# ME433_2017_PCB_mk2.net
KiCad netlist of a schematic drawn in EAGLE
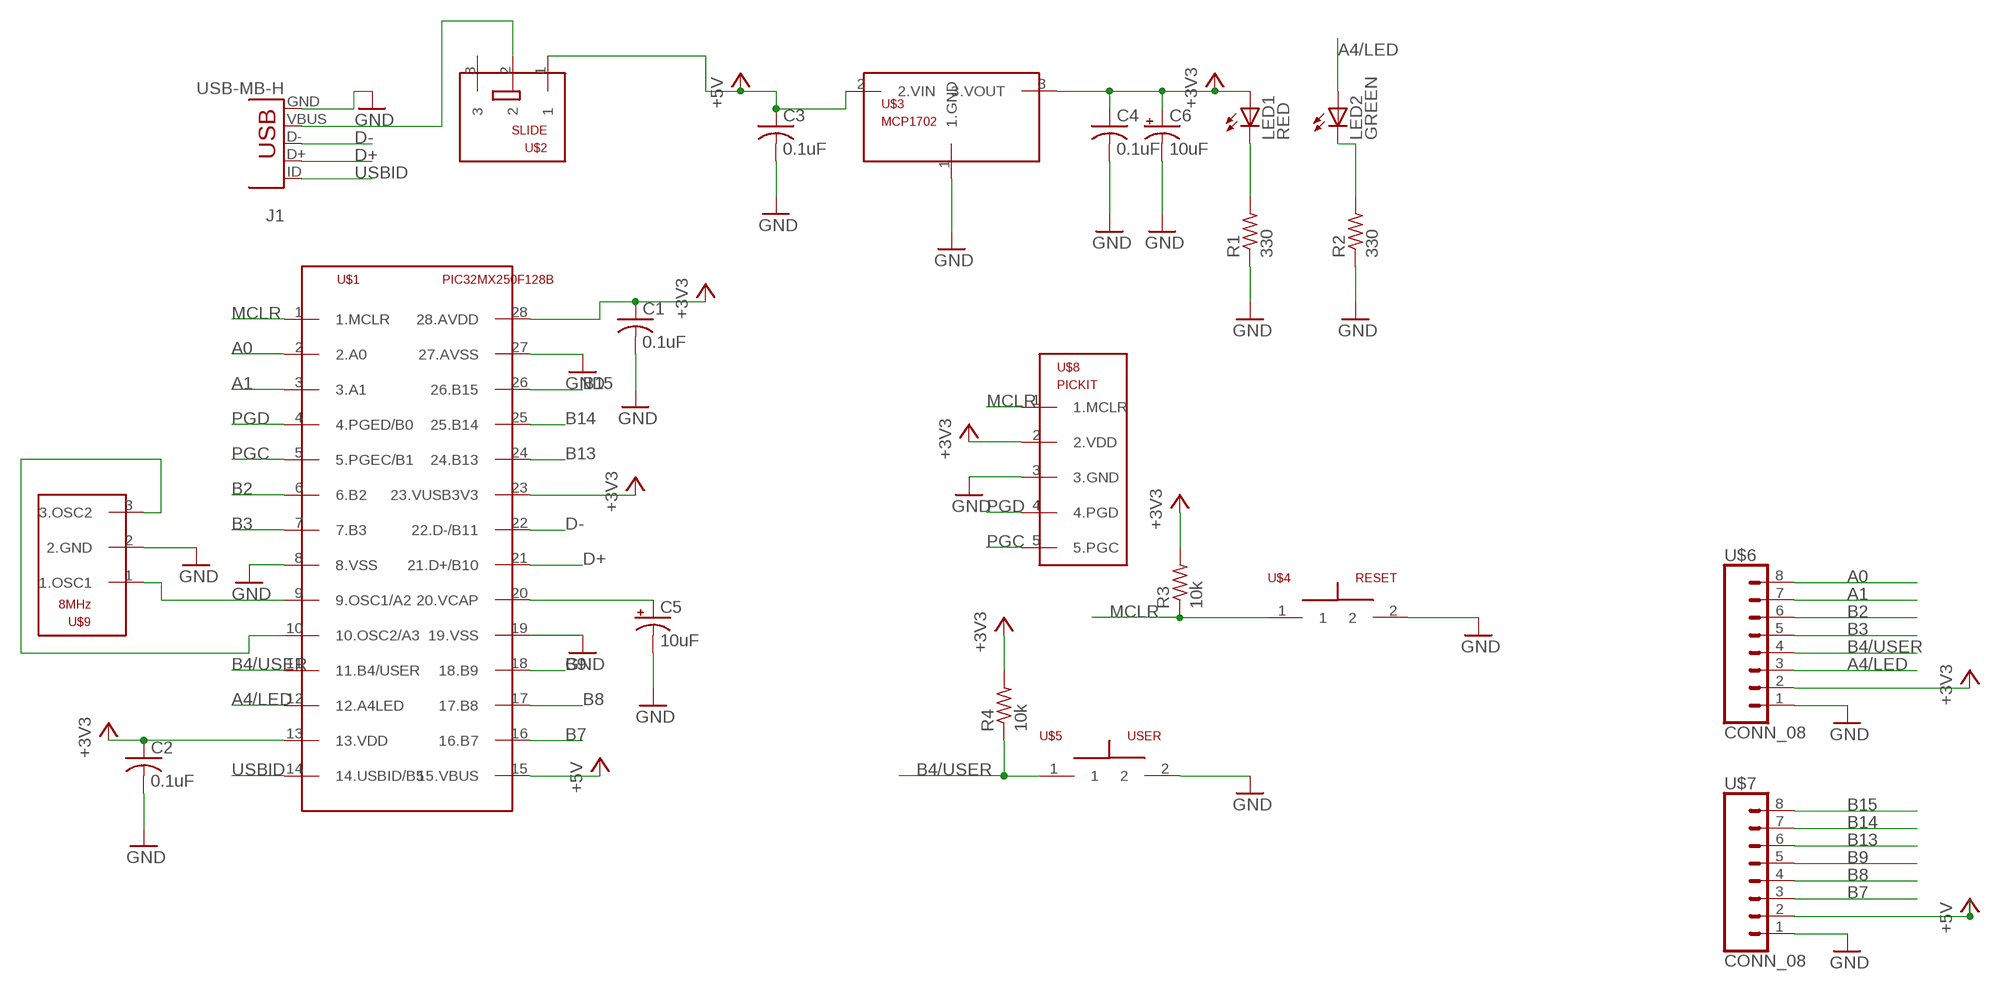
[diagram p0: schematic, sheet 1]

(export (version "E")
  (design (tool "Eeschema 10.0.6"))
  (components
    (comp (ref "C1")
      (value "0.1uF")
      (footprint "eagle-import:C025-025X050")
      (libsource (lib "eagle-import") (part "C-US025-025X050"))
    )
    (comp (ref "C2")
      (value "0.1uF")
      (footprint "eagle-import:C025-025X050")
      (libsource (lib "eagle-import") (part "C-US025-025X050"))
    )
    (comp (ref "C3")
      (value "0.1uF")
      (footprint "eagle-import:C025-025X050")
      (libsource (lib "eagle-import") (part "C-US025-025X050"))
    )
    (comp (ref "C4")
      (value "0.1uF")
      (footprint "eagle-import:C025-025X050")
      (libsource (lib "eagle-import") (part "C-US025-025X050"))
    )
    (comp (ref "C5")
      (value "10uF")
      (footprint "eagle-import:B45181B")
      (libsource (lib "eagle-import") (part "CPOL-USB45181B"))
    )
    (comp (ref "C6")
      (value "10uF")
      (footprint "eagle-import:B45181B")
      (libsource (lib "eagle-import") (part "CPOL-USB45181B"))
    )
    (comp (ref "J1")
      (value "USB-MB-H")
      (footprint "eagle-import:USB-MB-H")
      (libsource (lib "eagle-import") (part "USB-MB-H"))
    )
    (comp (ref "LED1")
      (value "RED")
      (footprint "eagle-import:LED3MM")
      (libsource (lib "eagle-import") (part "LED3MM"))
    )
    (comp (ref "LED2")
      (value "GREEN")
      (footprint "eagle-import:LED3MM")
      (libsource (lib "eagle-import") (part "LED3MM"))
    )
    (comp (ref "R1")
      (value "330")
      (footprint "eagle-import:0207_10")
      (libsource (lib "eagle-import") (part "R-US_0207/10"))
    )
    (comp (ref "R2")
      (value "330")
      (footprint "eagle-import:0207_10")
      (libsource (lib "eagle-import") (part "R-US_0207/10"))
    )
    (comp (ref "R3")
      (value "10k")
      (footprint "eagle-import:0207_10")
      (libsource (lib "eagle-import") (part "R-US_0207/10"))
    )
    (comp (ref "R4")
      (value "10k")
      (footprint "eagle-import:0207_10")
      (libsource (lib "eagle-import") (part "R-US_0207/10"))
    )
    (comp (ref "U$1")
      (value "PIC32MX250F128B")
      (footprint "eagle-import:DIL28-3")
      (libsource (lib "eagle-import") (part "PIC32MX250F128B"))
    )
    (comp (ref "U$2")
      (value "SLIDE")
      (footprint "eagle-import:SLIDE")
      (libsource (lib "eagle-import") (part "SLIDE"))
    )
    (comp (ref "U$3")
      (value "MCP1702")
      (footprint "eagle-import:TO92")
      (libsource (lib "eagle-import") (part "MCP1702"))
    )
    (comp (ref "U$4")
      (value "RESET")
      (footprint "eagle-import:BUTTON")
      (libsource (lib "eagle-import") (part "BUTTON"))
    )
    (comp (ref "U$5")
      (value "USER")
      (footprint "eagle-import:BUTTON")
      (libsource (lib "eagle-import") (part "BUTTON"))
    )
    (comp (ref "U$6")
      (value "CONN_08")
      (footprint "eagle-import:1X08")
      (libsource (lib "eagle-import") (part "CONN_08"))
    )
    (comp (ref "U$7")
      (value "CONN_08")
      (footprint "eagle-import:1X08")
      (libsource (lib "eagle-import") (part "CONN_08"))
    )
    (comp (ref "U$8")
      (value "PICKIT")
      (footprint "eagle-import:1X05")
      (libsource (lib "eagle-import") (part "PICKIT"))
    )
    (comp (ref "U$9")
      (value "8MHz")
      (footprint "eagle-import:OSC")
      (libsource (lib "eagle-import") (part "OSC"))
    )
  )
  (nets
    (net (code "1") (name "+3V3") (class "Default")
      (node (ref "C1") (pin "1") (pinfunction "1_1") (pintype "passive"))
      (node (ref "C2") (pin "1") (pinfunction "1_1") (pintype "passive"))
      (node (ref "C4") (pin "1") (pinfunction "1_1") (pintype "passive"))
      (node (ref "C6") (pin "+") (pinfunction "+_+") (pintype "passive"))
      (node (ref "LED1") (pin "A") (pinfunction "A_A") (pintype "passive"))
      (node (ref "R3") (pin "2") (pinfunction "2_2") (pintype "passive"))
      (node (ref "R4") (pin "2") (pinfunction "2_2") (pintype "passive"))
      (node (ref "U$1") (pin "13") (pinfunction "13.VDD_13") (pintype "bidirectional"))
      (node (ref "U$1") (pin "23") (pinfunction "23.VUSB3V3_23") (pintype "bidirectional"))
      (node (ref "U$1") (pin "28") (pinfunction "28.AVDD_28") (pintype "bidirectional"))
      (node (ref "U$3") (pin "3") (pinfunction "3.VOUT_3") (pintype "bidirectional"))
      (node (ref "U$6") (pin "2") (pinfunction "2_2") (pintype "passive"))
      (node (ref "U$8") (pin "2") (pinfunction "2.VDD_2") (pintype "bidirectional"))
    )
    (net (code "2") (name "+5V") (class "Default")
      (node (ref "C3") (pin "1") (pinfunction "1_1") (pintype "passive"))
      (node (ref "U$1") (pin "15") (pinfunction "15.VBUS_15") (pintype "bidirectional"))
      (node (ref "U$2") (pin "1") (pinfunction "1_1") (pintype "bidirectional"))
      (node (ref "U$3") (pin "2") (pinfunction "2.VIN_2") (pintype "bidirectional"))
      (node (ref "U$7") (pin "2") (pinfunction "2_2") (pintype "passive"))
    )
    (net (code "3") (name "/A0") (class "Default")
      (node (ref "U$1") (pin "2") (pinfunction "2.A0_2") (pintype "bidirectional"))
      (node (ref "U$6") (pin "8") (pinfunction "8_8") (pintype "passive"))
    )
    (net (code "4") (name "/A1") (class "Default")
      (node (ref "U$1") (pin "3") (pinfunction "3.A1_3") (pintype "bidirectional"))
      (node (ref "U$6") (pin "7") (pinfunction "7_7") (pintype "passive"))
    )
    (net (code "5") (name "/A4{slash}LED") (class "Default")
      (node (ref "LED2") (pin "A") (pinfunction "A_A") (pintype "passive"))
      (node (ref "U$1") (pin "12") (pinfunction "12.A4LED_12") (pintype "bidirectional"))
      (node (ref "U$6") (pin "3") (pinfunction "3_3") (pintype "passive"))
    )
    (net (code "6") (name "/B2") (class "Default")
      (node (ref "U$1") (pin "6") (pinfunction "6.B2_6") (pintype "bidirectional"))
      (node (ref "U$6") (pin "6") (pinfunction "6_6") (pintype "passive"))
    )
    (net (code "7") (name "/B3") (class "Default")
      (node (ref "U$1") (pin "7") (pinfunction "7.B3_7") (pintype "bidirectional"))
      (node (ref "U$6") (pin "5") (pinfunction "5_5") (pintype "passive"))
    )
    (net (code "8") (name "/B4{slash}USER") (class "Default")
      (node (ref "R4") (pin "1") (pinfunction "1_1") (pintype "passive"))
      (node (ref "U$1") (pin "11") (pinfunction "11.B4/USER_11") (pintype "bidirectional"))
      (node (ref "U$5") (pin "1") (pinfunction "1_1") (pintype "bidirectional"))
      (node (ref "U$6") (pin "4") (pinfunction "4_4") (pintype "passive"))
    )
    (net (code "9") (name "/B7") (class "Default")
      (node (ref "U$1") (pin "16") (pinfunction "16.B7_16") (pintype "bidirectional"))
      (node (ref "U$7") (pin "3") (pinfunction "3_3") (pintype "passive"))
    )
    (net (code "10") (name "/B8") (class "Default")
      (node (ref "U$1") (pin "17") (pinfunction "17.B8_17") (pintype "bidirectional"))
      (node (ref "U$7") (pin "4") (pinfunction "4_4") (pintype "passive"))
    )
    (net (code "11") (name "/B9") (class "Default")
      (node (ref "U$1") (pin "18") (pinfunction "18.B9_18") (pintype "bidirectional"))
      (node (ref "U$7") (pin "5") (pinfunction "5_5") (pintype "passive"))
    )
    (net (code "12") (name "/B13") (class "Default")
      (node (ref "U$1") (pin "24") (pinfunction "24.B13_24") (pintype "bidirectional"))
      (node (ref "U$7") (pin "6") (pinfunction "6_6") (pintype "passive"))
    )
    (net (code "13") (name "/B14") (class "Default")
      (node (ref "U$1") (pin "25") (pinfunction "25.B14_25") (pintype "bidirectional"))
      (node (ref "U$7") (pin "7") (pinfunction "7_7") (pintype "passive"))
    )
    (net (code "14") (name "/B15") (class "Default")
      (node (ref "U$1") (pin "26") (pinfunction "26.B15_26") (pintype "bidirectional"))
      (node (ref "U$7") (pin "8") (pinfunction "8_8") (pintype "passive"))
    )
    (net (code "15") (name "/D+") (class "Default")
      (node (ref "J1") (pin "D+") (pinfunction "D+_D+") (pintype "bidirectional"))
      (node (ref "U$1") (pin "21") (pinfunction "21.D+/B10_21") (pintype "bidirectional"))
    )
    (net (code "16") (name "/D-") (class "Default")
      (node (ref "J1") (pin "D-") (pinfunction "D-_D-") (pintype "bidirectional"))
      (node (ref "U$1") (pin "22") (pinfunction "22.D-/B11_22") (pintype "bidirectional"))
    )
    (net (code "17") (name "/MCLR") (class "Default")
      (node (ref "R3") (pin "1") (pinfunction "1_1") (pintype "passive"))
      (node (ref "U$1") (pin "1") (pinfunction "1.MCLR_1") (pintype "bidirectional"))
      (node (ref "U$4") (pin "1") (pinfunction "1_1") (pintype "bidirectional"))
      (node (ref "U$8") (pin "1") (pinfunction "1.MCLR_1") (pintype "bidirectional"))
    )
    (net (code "18") (name "/PGC") (class "Default")
      (node (ref "U$1") (pin "5") (pinfunction "5.PGEC/B1_5") (pintype "bidirectional"))
      (node (ref "U$8") (pin "5") (pinfunction "5.PGC_5") (pintype "bidirectional"))
    )
    (net (code "19") (name "/PGD") (class "Default")
      (node (ref "U$1") (pin "4") (pinfunction "4.PGED/B0_4") (pintype "bidirectional"))
      (node (ref "U$8") (pin "4") (pinfunction "4.PGD_4") (pintype "bidirectional"))
    )
    (net (code "20") (name "/USBID") (class "Default")
      (node (ref "J1") (pin "ID") (pinfunction "ID_ID") (pintype "bidirectional"))
      (node (ref "U$1") (pin "14") (pinfunction "14.USBID/B5_14") (pintype "bidirectional"))
    )
    (net (code "21") (name "GND") (class "Default")
      (node (ref "C1") (pin "2") (pinfunction "2_2") (pintype "passive"))
      (node (ref "C2") (pin "2") (pinfunction "2_2") (pintype "passive"))
      (node (ref "C3") (pin "2") (pinfunction "2_2") (pintype "passive"))
      (node (ref "C4") (pin "2") (pinfunction "2_2") (pintype "passive"))
      (node (ref "C5") (pin "-") (pinfunction "-_-") (pintype "passive"))
      (node (ref "C6") (pin "-") (pinfunction "-_-") (pintype "passive"))
      (node (ref "J1") (pin "GND") (pinfunction "GND_GND") (pintype "bidirectional"))
      (node (ref "R1") (pin "1") (pinfunction "1_1") (pintype "passive"))
      (node (ref "R2") (pin "1") (pinfunction "1_1") (pintype "passive"))
      (node (ref "U$1") (pin "19") (pinfunction "19.VSS_19") (pintype "bidirectional"))
      (node (ref "U$1") (pin "27") (pinfunction "27.AVSS_27") (pintype "bidirectional"))
      (node (ref "U$1") (pin "8") (pinfunction "8.VSS_8") (pintype "bidirectional"))
      (node (ref "U$3") (pin "1") (pinfunction "1.GND_1") (pintype "bidirectional"))
      (node (ref "U$4") (pin "2") (pinfunction "2_2") (pintype "bidirectional"))
      (node (ref "U$5") (pin "2") (pinfunction "2_2") (pintype "bidirectional"))
      (node (ref "U$6") (pin "1") (pinfunction "1_1") (pintype "passive"))
      (node (ref "U$7") (pin "1") (pinfunction "1_1") (pintype "passive"))
      (node (ref "U$8") (pin "3") (pinfunction "3.GND_3") (pintype "bidirectional"))
      (node (ref "U$9") (pin "2") (pinfunction "2.GND_2") (pintype "bidirectional"))
    )
    (net (code "22") (name "Net-(J1-PadVBUS)") (class "Default")
      (node (ref "J1") (pin "VBUS") (pinfunction "VBUS_VBUS") (pintype "bidirectional"))
      (node (ref "U$2") (pin "2") (pinfunction "2_2") (pintype "bidirectional"))
    )
    (net (code "23") (name "Net-(LED1-C)") (class "Default")
      (node (ref "LED1") (pin "K") (pinfunction "C_K") (pintype "passive"))
      (node (ref "R1") (pin "2") (pinfunction "2_2") (pintype "passive"))
    )
    (net (code "24") (name "Net-(LED2-C)") (class "Default")
      (node (ref "LED2") (pin "K") (pinfunction "C_K") (pintype "passive"))
      (node (ref "R2") (pin "2") (pinfunction "2_2") (pintype "passive"))
    )
    (net (code "25") (name "Net-(U$1-9.OSC1{slash}A2)") (class "Default")
      (node (ref "U$1") (pin "9") (pinfunction "9.OSC1/A2_9") (pintype "bidirectional"))
      (node (ref "U$9") (pin "1") (pinfunction "1.OSC1_1") (pintype "bidirectional"))
    )
    (net (code "26") (name "Net-(U$1-10.OSC2{slash}A3)") (class "Default")
      (node (ref "U$1") (pin "10") (pinfunction "10.OSC2/A3_10") (pintype "bidirectional"))
      (node (ref "U$9") (pin "3") (pinfunction "3.OSC2_3") (pintype "bidirectional"))
    )
    (net (code "27") (name "Net-(U$1-20.VCAP)") (class "Default")
      (node (ref "C5") (pin "+") (pinfunction "+_+") (pintype "passive"))
      (node (ref "U$1") (pin "20") (pinfunction "20.VCAP_20") (pintype "bidirectional"))
    )
    (net (code "28") (name "unconnected-(U$2-Pad3)") (class "Default")
      (node (ref "U$2") (pin "3") (pinfunction "3_3") (pintype "bidirectional"))
    )
  )
)
